# TCduo_v1.net
KiCad netlist of a schematic drawn in EAGLE
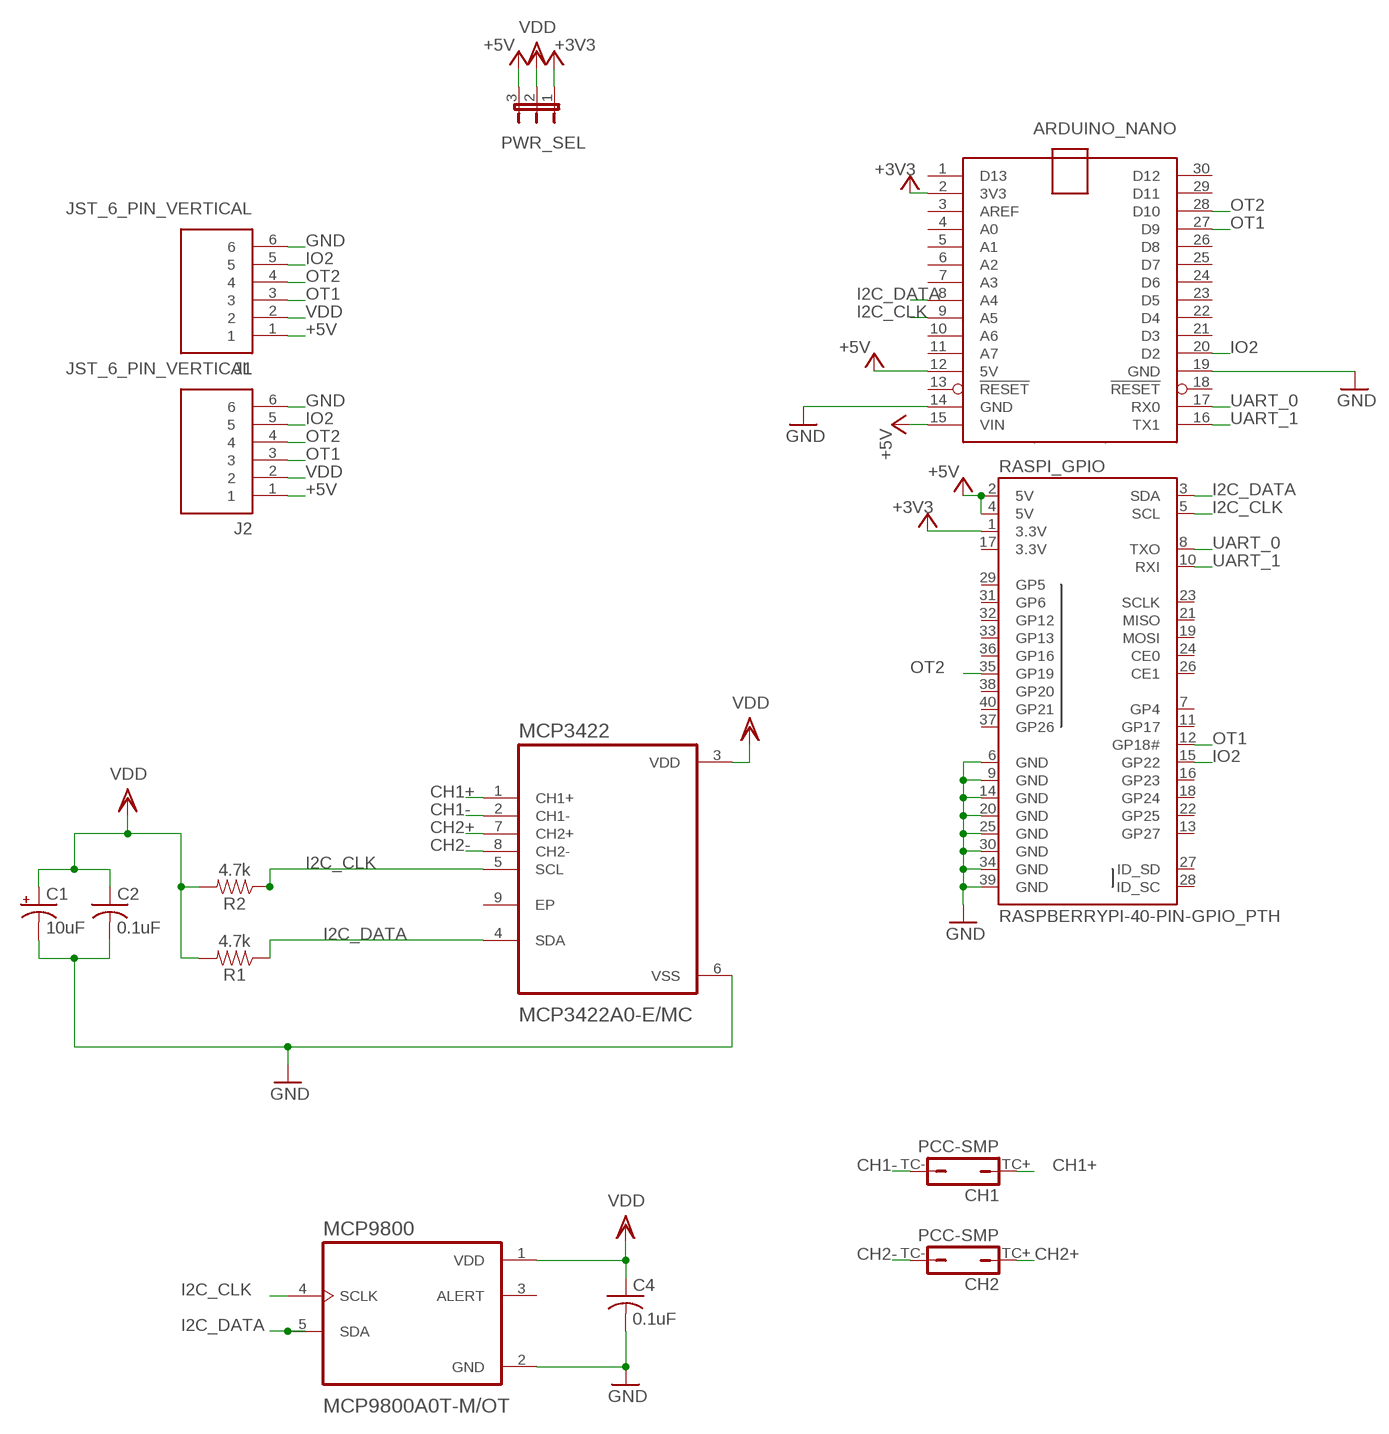
[diagram p0: schematic, sheet 1]

(export (version "E")
  (design (tool "Eeschema 10.0.6"))
  (components
    (comp (ref "ARDUINO_NANO")
      (value "ARDUINO_NANO")
      (footprint "eagle-import:ARDUINO_NANO")
      (libsource (lib "eagle-import") (part "ARDUINO_NANO"))
    )
    (comp (ref "C1")
      (value "10uF")
      (footprint "eagle-import:EIA3216")
      (libsource (lib "eagle-import") (part "10UF-POLAR-EIA3216-16V-10%(TANT)"))
    )
    (comp (ref "C2")
      (value "0.1uF")
      (footprint "eagle-import:C0805")
      (libsource (lib "eagle-import") (part "C-USC0805"))
    )
    (comp (ref "C4")
      (value "0.1uF")
      (footprint "eagle-import:C0805")
      (libsource (lib "eagle-import") (part "C-USC0805"))
    )
    (comp (ref "CH1")
      (value "PCC-SMP")
      (footprint "eagle-import:PCC-SMP")
      (libsource (lib "eagle-import") (part "PCC-SMP"))
    )
    (comp (ref "CH2")
      (value "PCC-SMP")
      (footprint "eagle-import:PCC-SMP")
      (libsource (lib "eagle-import") (part "PCC-SMP"))
    )
    (comp (ref "J1")
      (value "JST_6_PIN_VERTICAL")
      (footprint "eagle-import:JST-6-SMD-VERT-1.0MM")
      (libsource (lib "eagle-import") (part "JST_6_PIN_VERTICAL"))
    )
    (comp (ref "J2")
      (value "JST_6_PIN_VERTICAL")
      (footprint "eagle-import:JST-6-SMD-VERT-1.0MM")
      (libsource (lib "eagle-import") (part "JST_6_PIN_VERTICAL"))
    )
    (comp (ref "MCP3422")
      (value "MCP3422A0-E/MC")
      (footprint "eagle-import:SON50P200X300X100-9N")
      (fields (field (name "DIGI-KEY_PART_NUMBER") "MCP3422A0-E/MC-ND") (field (name "MF") "Microchip"))
      (libsource (lib "eagle-import") (part "MCP3422A0-E/MC"))
    )
    (comp (ref "MCP9800")
      (value "MCP9800A0T-M/OT")
      (footprint "eagle-import:SOT95P270X145-5N")
      (fields (field (name "DIGI-KEY_PART_NUMBER") "MCP9800A0T-M/OTCT-ND") (field (name "MF") "Microchip"))
      (libsource (lib "eagle-import") (part "MCP9800A0T-M/OT"))
    )
    (comp (ref "PWR_SEL")
      (value "JP2E")
      (footprint "eagle-import:JP2")
      (libsource (lib "eagle-import") (part "JP2E"))
    )
    (comp (ref "R1")
      (value "4.7k")
      (footprint "eagle-import:0603")
      (libsource (lib "eagle-import") (part "4.7KOHM-0603-1/10W-1%"))
    )
    (comp (ref "R2")
      (value "4.7k")
      (footprint "eagle-import:0603")
      (libsource (lib "eagle-import") (part "4.7KOHM-0603-1/10W-1%"))
    )
    (comp (ref "RASPI_GPIO")
      (value "RASPBERRYPI-40-PIN-GPIO_PTH")
      (footprint "eagle-import:2X20_SHROUDED")
      (libsource (lib "eagle-import") (part "RASPBERRYPI-40-PIN-GPIO_PTH"))
    )
  )
  (nets
    (net (code "1") (name "+3V3") (class "Default")
      (node (ref "ARDUINO_NANO") (pin "2") (pinfunction "3V3_2") (pintype "output"))
      (node (ref "PWR_SEL") (pin "1") (pinfunction "1_1") (pintype "passive"))
      (node (ref "RASPI_GPIO") (pin "1") (pinfunction "3.3V_1") (pintype "power_in"))
    )
    (net (code "2") (name "+5V") (class "Default")
      (node (ref "ARDUINO_NANO") (pin "12") (pinfunction "5V_12") (pintype "power_in"))
      (node (ref "ARDUINO_NANO") (pin "15") (pinfunction "VIN_15") (pintype "power_in"))
      (node (ref "J1") (pin "1") (pinfunction "1_1") (pintype "bidirectional"))
      (node (ref "J2") (pin "1") (pinfunction "1_1") (pintype "bidirectional"))
      (node (ref "PWR_SEL") (pin "3") (pinfunction "3_3") (pintype "passive"))
      (node (ref "RASPI_GPIO") (pin "2") (pinfunction "5V_2") (pintype "power_in"))
      (node (ref "RASPI_GPIO") (pin "4") (pinfunction "5V_4") (pintype "power_in"))
    )
    (net (code "3") (name "/3.3V") (class "Default")
      (node (ref "RASPI_GPIO") (pin "17") (pinfunction "3.3V_17") (pintype "power_in"))
    )
    (net (code "4") (name "/CH1+") (class "Default")
      (node (ref "CH1") (pin "TC+") (pinfunction "1_TC+") (pintype "passive"))
      (node (ref "MCP3422") (pin "1") (pinfunction "CH1+_1") (pintype "input"))
    )
    (net (code "5") (name "/CH1-") (class "Default")
      (node (ref "CH1") (pin "TC-") (pinfunction "2_TC-") (pintype "passive"))
      (node (ref "MCP3422") (pin "2") (pinfunction "CH1-_2") (pintype "input"))
    )
    (net (code "6") (name "/CH2+") (class "Default")
      (node (ref "CH2") (pin "TC+") (pinfunction "1_TC+") (pintype "passive"))
      (node (ref "MCP3422") (pin "7") (pinfunction "CH2+_7") (pintype "input"))
    )
    (net (code "7") (name "/CH2-") (class "Default")
      (node (ref "CH2") (pin "TC-") (pinfunction "2_TC-") (pintype "passive"))
      (node (ref "MCP3422") (pin "8") (pinfunction "CH2-_8") (pintype "input"))
    )
    (net (code "8") (name "/I2C_CLK") (class "Default")
      (node (ref "ARDUINO_NANO") (pin "9") (pinfunction "A5_9") (pintype "bidirectional"))
      (node (ref "MCP3422") (pin "5") (pinfunction "SCL_5") (pintype "input"))
      (node (ref "MCP9800") (pin "4") (pinfunction "SCLK_4") (pintype "input"))
      (node (ref "R2") (pin "1") (pinfunction "1_1") (pintype "passive"))
      (node (ref "RASPI_GPIO") (pin "5") (pinfunction "SCL_5") (pintype "bidirectional"))
    )
    (net (code "9") (name "/I2C_DATA") (class "Default")
      (node (ref "ARDUINO_NANO") (pin "8") (pinfunction "A4_8") (pintype "bidirectional"))
      (node (ref "MCP3422") (pin "4") (pinfunction "SDA_4") (pintype "bidirectional"))
      (node (ref "MCP9800") (pin "5") (pinfunction "SDA_5") (pintype "bidirectional"))
      (node (ref "R1") (pin "1") (pinfunction "1_1") (pintype "passive"))
      (node (ref "RASPI_GPIO") (pin "3") (pinfunction "SDA_3") (pintype "bidirectional"))
    )
    (net (code "10") (name "/IO2") (class "Default")
      (node (ref "ARDUINO_NANO") (pin "20") (pinfunction "D2_20") (pintype "bidirectional"))
      (node (ref "J1") (pin "5") (pinfunction "5_5") (pintype "bidirectional"))
      (node (ref "J2") (pin "5") (pinfunction "5_5") (pintype "bidirectional"))
      (node (ref "RASPI_GPIO") (pin "15") (pinfunction "GP22_15") (pintype "bidirectional"))
    )
    (net (code "11") (name "/OT1") (class "Default")
      (node (ref "ARDUINO_NANO") (pin "27") (pinfunction "D9_27") (pintype "bidirectional"))
      (node (ref "J1") (pin "3") (pinfunction "3_3") (pintype "bidirectional"))
      (node (ref "J2") (pin "3") (pinfunction "3_3") (pintype "bidirectional"))
      (node (ref "RASPI_GPIO") (pin "12") (pinfunction "GP18#_12") (pintype "bidirectional"))
    )
    (net (code "12") (name "/OT2") (class "Default")
      (node (ref "ARDUINO_NANO") (pin "28") (pinfunction "D10_28") (pintype "bidirectional"))
      (node (ref "J1") (pin "4") (pinfunction "4_4") (pintype "bidirectional"))
      (node (ref "J2") (pin "4") (pinfunction "4_4") (pintype "bidirectional"))
      (node (ref "RASPI_GPIO") (pin "35") (pinfunction "GP19_35") (pintype "bidirectional"))
    )
    (net (code "13") (name "/UART_0") (class "Default")
      (node (ref "ARDUINO_NANO") (pin "17") (pinfunction "RX0_17") (pintype "bidirectional"))
      (node (ref "RASPI_GPIO") (pin "8") (pinfunction "TXO_8") (pintype "output"))
    )
    (net (code "14") (name "/UART_1") (class "Default")
      (node (ref "ARDUINO_NANO") (pin "16") (pinfunction "TX1_16") (pintype "bidirectional"))
      (node (ref "RASPI_GPIO") (pin "10") (pinfunction "RXI_10") (pintype "input"))
    )
    (net (code "15") (name "GND") (class "Default")
      (node (ref "ARDUINO_NANO") (pin "14") (pinfunction "GND_14") (pintype "power_in"))
      (node (ref "ARDUINO_NANO") (pin "19") (pinfunction "GND_19") (pintype "power_in"))
      (node (ref "C1") (pin "-") (pinfunction "-_-") (pintype "passive"))
      (node (ref "C2") (pin "2") (pinfunction "2_2") (pintype "passive"))
      (node (ref "C4") (pin "2") (pinfunction "2_2") (pintype "passive"))
      (node (ref "J1") (pin "6") (pinfunction "6_6") (pintype "bidirectional"))
      (node (ref "J2") (pin "6") (pinfunction "6_6") (pintype "bidirectional"))
      (node (ref "MCP3422") (pin "6") (pinfunction "VSS_6") (pintype "power_in"))
      (node (ref "MCP9800") (pin "2") (pinfunction "GND_2") (pintype "power_in"))
      (node (ref "RASPI_GPIO") (pin "14") (pinfunction "GND_14") (pintype "power_in"))
      (node (ref "RASPI_GPIO") (pin "20") (pinfunction "GND_20") (pintype "power_in"))
      (node (ref "RASPI_GPIO") (pin "25") (pinfunction "GND_25") (pintype "power_in"))
      (node (ref "RASPI_GPIO") (pin "30") (pinfunction "GND_30") (pintype "power_in"))
      (node (ref "RASPI_GPIO") (pin "34") (pinfunction "GND_34") (pintype "power_in"))
      (node (ref "RASPI_GPIO") (pin "39") (pinfunction "GND_39") (pintype "power_in"))
      (node (ref "RASPI_GPIO") (pin "6") (pinfunction "GND_6") (pintype "power_in"))
      (node (ref "RASPI_GPIO") (pin "9") (pinfunction "GND_9") (pintype "power_in"))
    )
    (net (code "16") (name "VDD") (class "Default")
      (node (ref "C1") (pin "+") (pinfunction "+_+") (pintype "passive"))
      (node (ref "C2") (pin "1") (pinfunction "1_1") (pintype "passive"))
      (node (ref "C4") (pin "1") (pinfunction "1_1") (pintype "passive"))
      (node (ref "J1") (pin "2") (pinfunction "2_2") (pintype "bidirectional"))
      (node (ref "J2") (pin "2") (pinfunction "2_2") (pintype "bidirectional"))
      (node (ref "MCP3422") (pin "3") (pinfunction "VDD_3") (pintype "power_in"))
      (node (ref "MCP9800") (pin "1") (pinfunction "VDD_1") (pintype "power_in"))
      (node (ref "PWR_SEL") (pin "2") (pinfunction "2_2") (pintype "passive"))
      (node (ref "R1") (pin "2") (pinfunction "2_2") (pintype "passive"))
      (node (ref "R2") (pin "2") (pinfunction "2_2") (pintype "passive"))
    )
    (net (code "17") (name "unconnected-(ARDUINO_NANO-A0-Pad4)") (class "Default")
      (node (ref "ARDUINO_NANO") (pin "4") (pinfunction "A0_4") (pintype "bidirectional"))
    )
    (net (code "18") (name "unconnected-(ARDUINO_NANO-A1-Pad5)") (class "Default")
      (node (ref "ARDUINO_NANO") (pin "5") (pinfunction "A1_5") (pintype "bidirectional"))
    )
    (net (code "19") (name "unconnected-(ARDUINO_NANO-A2-Pad6)") (class "Default")
      (node (ref "ARDUINO_NANO") (pin "6") (pinfunction "A2_6") (pintype "bidirectional"))
    )
    (net (code "20") (name "unconnected-(ARDUINO_NANO-A3-Pad7)") (class "Default")
      (node (ref "ARDUINO_NANO") (pin "7") (pinfunction "A3_7") (pintype "bidirectional"))
    )
    (net (code "21") (name "unconnected-(ARDUINO_NANO-A6-Pad10)") (class "Default")
      (node (ref "ARDUINO_NANO") (pin "10") (pinfunction "A6_10") (pintype "bidirectional"))
    )
    (net (code "22") (name "unconnected-(ARDUINO_NANO-A7-Pad11)") (class "Default")
      (node (ref "ARDUINO_NANO") (pin "11") (pinfunction "A7_11") (pintype "bidirectional"))
    )
    (net (code "23") (name "unconnected-(ARDUINO_NANO-AREF-Pad3)") (class "Default")
      (node (ref "ARDUINO_NANO") (pin "3") (pinfunction "AREF_3") (pintype "input"))
    )
    (net (code "24") (name "unconnected-(ARDUINO_NANO-D3-Pad21)") (class "Default")
      (node (ref "ARDUINO_NANO") (pin "21") (pinfunction "D3_21") (pintype "bidirectional"))
    )
    (net (code "25") (name "unconnected-(ARDUINO_NANO-D4-Pad22)") (class "Default")
      (node (ref "ARDUINO_NANO") (pin "22") (pinfunction "D4_22") (pintype "bidirectional"))
    )
    (net (code "26") (name "unconnected-(ARDUINO_NANO-D5-Pad23)") (class "Default")
      (node (ref "ARDUINO_NANO") (pin "23") (pinfunction "D5_23") (pintype "bidirectional"))
    )
    (net (code "27") (name "unconnected-(ARDUINO_NANO-D6-Pad24)") (class "Default")
      (node (ref "ARDUINO_NANO") (pin "24") (pinfunction "D6_24") (pintype "bidirectional"))
    )
    (net (code "28") (name "unconnected-(ARDUINO_NANO-D7-Pad25)") (class "Default")
      (node (ref "ARDUINO_NANO") (pin "25") (pinfunction "D7_25") (pintype "bidirectional"))
    )
    (net (code "29") (name "unconnected-(ARDUINO_NANO-D8-Pad26)") (class "Default")
      (node (ref "ARDUINO_NANO") (pin "26") (pinfunction "D8_26") (pintype "bidirectional"))
    )
    (net (code "30") (name "unconnected-(ARDUINO_NANO-D11-Pad29)") (class "Default")
      (node (ref "ARDUINO_NANO") (pin "29") (pinfunction "D11_29") (pintype "bidirectional"))
    )
    (net (code "31") (name "unconnected-(ARDUINO_NANO-D12-Pad30)") (class "Default")
      (node (ref "ARDUINO_NANO") (pin "30") (pinfunction "D12_30") (pintype "bidirectional"))
    )
    (net (code "32") (name "unconnected-(ARDUINO_NANO-D13-Pad1)") (class "Default")
      (node (ref "ARDUINO_NANO") (pin "1") (pinfunction "D13_1") (pintype "bidirectional"))
    )
    (net (code "33") (name "unconnected-(ARDUINO_NANO-~{RESET}-Pad13)") (class "Default")
      (node (ref "ARDUINO_NANO") (pin "13") (pinfunction "~{RESET}_13") (pintype "input"))
    )
    (net (code "34") (name "unconnected-(ARDUINO_NANO-~{RESET}-Pad18)") (class "Default")
      (node (ref "ARDUINO_NANO") (pin "18") (pinfunction "~{RESET}_18") (pintype "input"))
    )
    (net (code "35") (name "unconnected-(MCP3422-EP-Pad9)") (class "Default")
      (node (ref "MCP3422") (pin "9") (pinfunction "EP_9") (pintype "bidirectional"))
    )
    (net (code "36") (name "unconnected-(MCP9800-ALERT-Pad3)") (class "Default")
      (node (ref "MCP9800") (pin "3") (pinfunction "ALERT_3") (pintype "output"))
    )
    (net (code "37") (name "unconnected-(RASPI_GPIO-CE0-Pad24)") (class "Default")
      (node (ref "RASPI_GPIO") (pin "24") (pinfunction "CE0_24") (pintype "output"))
    )
    (net (code "38") (name "unconnected-(RASPI_GPIO-CE1-Pad26)") (class "Default")
      (node (ref "RASPI_GPIO") (pin "26") (pinfunction "CE1_26") (pintype "output"))
    )
    (net (code "39") (name "unconnected-(RASPI_GPIO-GP4-Pad7)") (class "Default")
      (node (ref "RASPI_GPIO") (pin "7") (pinfunction "GP4_7") (pintype "bidirectional"))
    )
    (net (code "40") (name "unconnected-(RASPI_GPIO-GP5-Pad29)") (class "Default")
      (node (ref "RASPI_GPIO") (pin "29") (pinfunction "GP5_29") (pintype "bidirectional"))
    )
    (net (code "41") (name "unconnected-(RASPI_GPIO-GP6-Pad31)") (class "Default")
      (node (ref "RASPI_GPIO") (pin "31") (pinfunction "GP6_31") (pintype "bidirectional"))
    )
    (net (code "42") (name "unconnected-(RASPI_GPIO-GP12-Pad32)") (class "Default")
      (node (ref "RASPI_GPIO") (pin "32") (pinfunction "GP12_32") (pintype "bidirectional"))
    )
    (net (code "43") (name "unconnected-(RASPI_GPIO-GP13-Pad33)") (class "Default")
      (node (ref "RASPI_GPIO") (pin "33") (pinfunction "GP13_33") (pintype "bidirectional"))
    )
    (net (code "44") (name "unconnected-(RASPI_GPIO-GP16-Pad36)") (class "Default")
      (node (ref "RASPI_GPIO") (pin "36") (pinfunction "GP16_36") (pintype "bidirectional"))
    )
    (net (code "45") (name "unconnected-(RASPI_GPIO-GP17-Pad11)") (class "Default")
      (node (ref "RASPI_GPIO") (pin "11") (pinfunction "GP17_11") (pintype "bidirectional"))
    )
    (net (code "46") (name "unconnected-(RASPI_GPIO-GP20-Pad38)") (class "Default")
      (node (ref "RASPI_GPIO") (pin "38") (pinfunction "GP20_38") (pintype "bidirectional"))
    )
    (net (code "47") (name "unconnected-(RASPI_GPIO-GP21-Pad40)") (class "Default")
      (node (ref "RASPI_GPIO") (pin "40") (pinfunction "GP21_40") (pintype "bidirectional"))
    )
    (net (code "48") (name "unconnected-(RASPI_GPIO-GP23-Pad16)") (class "Default")
      (node (ref "RASPI_GPIO") (pin "16") (pinfunction "GP23_16") (pintype "bidirectional"))
    )
    (net (code "49") (name "unconnected-(RASPI_GPIO-GP24-Pad18)") (class "Default")
      (node (ref "RASPI_GPIO") (pin "18") (pinfunction "GP24_18") (pintype "bidirectional"))
    )
    (net (code "50") (name "unconnected-(RASPI_GPIO-GP25-Pad22)") (class "Default")
      (node (ref "RASPI_GPIO") (pin "22") (pinfunction "GP25_22") (pintype "bidirectional"))
    )
    (net (code "51") (name "unconnected-(RASPI_GPIO-GP26-Pad37)") (class "Default")
      (node (ref "RASPI_GPIO") (pin "37") (pinfunction "GP26_37") (pintype "bidirectional"))
    )
    (net (code "52") (name "unconnected-(RASPI_GPIO-GP27-Pad13)") (class "Default")
      (node (ref "RASPI_GPIO") (pin "13") (pinfunction "GP27_13") (pintype "bidirectional"))
    )
    (net (code "53") (name "unconnected-(RASPI_GPIO-ID_SC-Pad28)") (class "Default")
      (node (ref "RASPI_GPIO") (pin "28") (pinfunction "ID_SC_28") (pintype "bidirectional"))
    )
    (net (code "54") (name "unconnected-(RASPI_GPIO-ID_SD-Pad27)") (class "Default")
      (node (ref "RASPI_GPIO") (pin "27") (pinfunction "ID_SD_27") (pintype "bidirectional"))
    )
    (net (code "55") (name "unconnected-(RASPI_GPIO-MISO-Pad21)") (class "Default")
      (node (ref "RASPI_GPIO") (pin "21") (pinfunction "MISO_21") (pintype "input"))
    )
    (net (code "56") (name "unconnected-(RASPI_GPIO-MOSI-Pad19)") (class "Default")
      (node (ref "RASPI_GPIO") (pin "19") (pinfunction "MOSI_19") (pintype "output"))
    )
    (net (code "57") (name "unconnected-(RASPI_GPIO-SCLK-Pad23)") (class "Default")
      (node (ref "RASPI_GPIO") (pin "23") (pinfunction "SCLK_23") (pintype "output"))
    )
  )
)
